# TUE-JJ-9-1.net
KiCad netlist of a schematic drawn in EAGLE
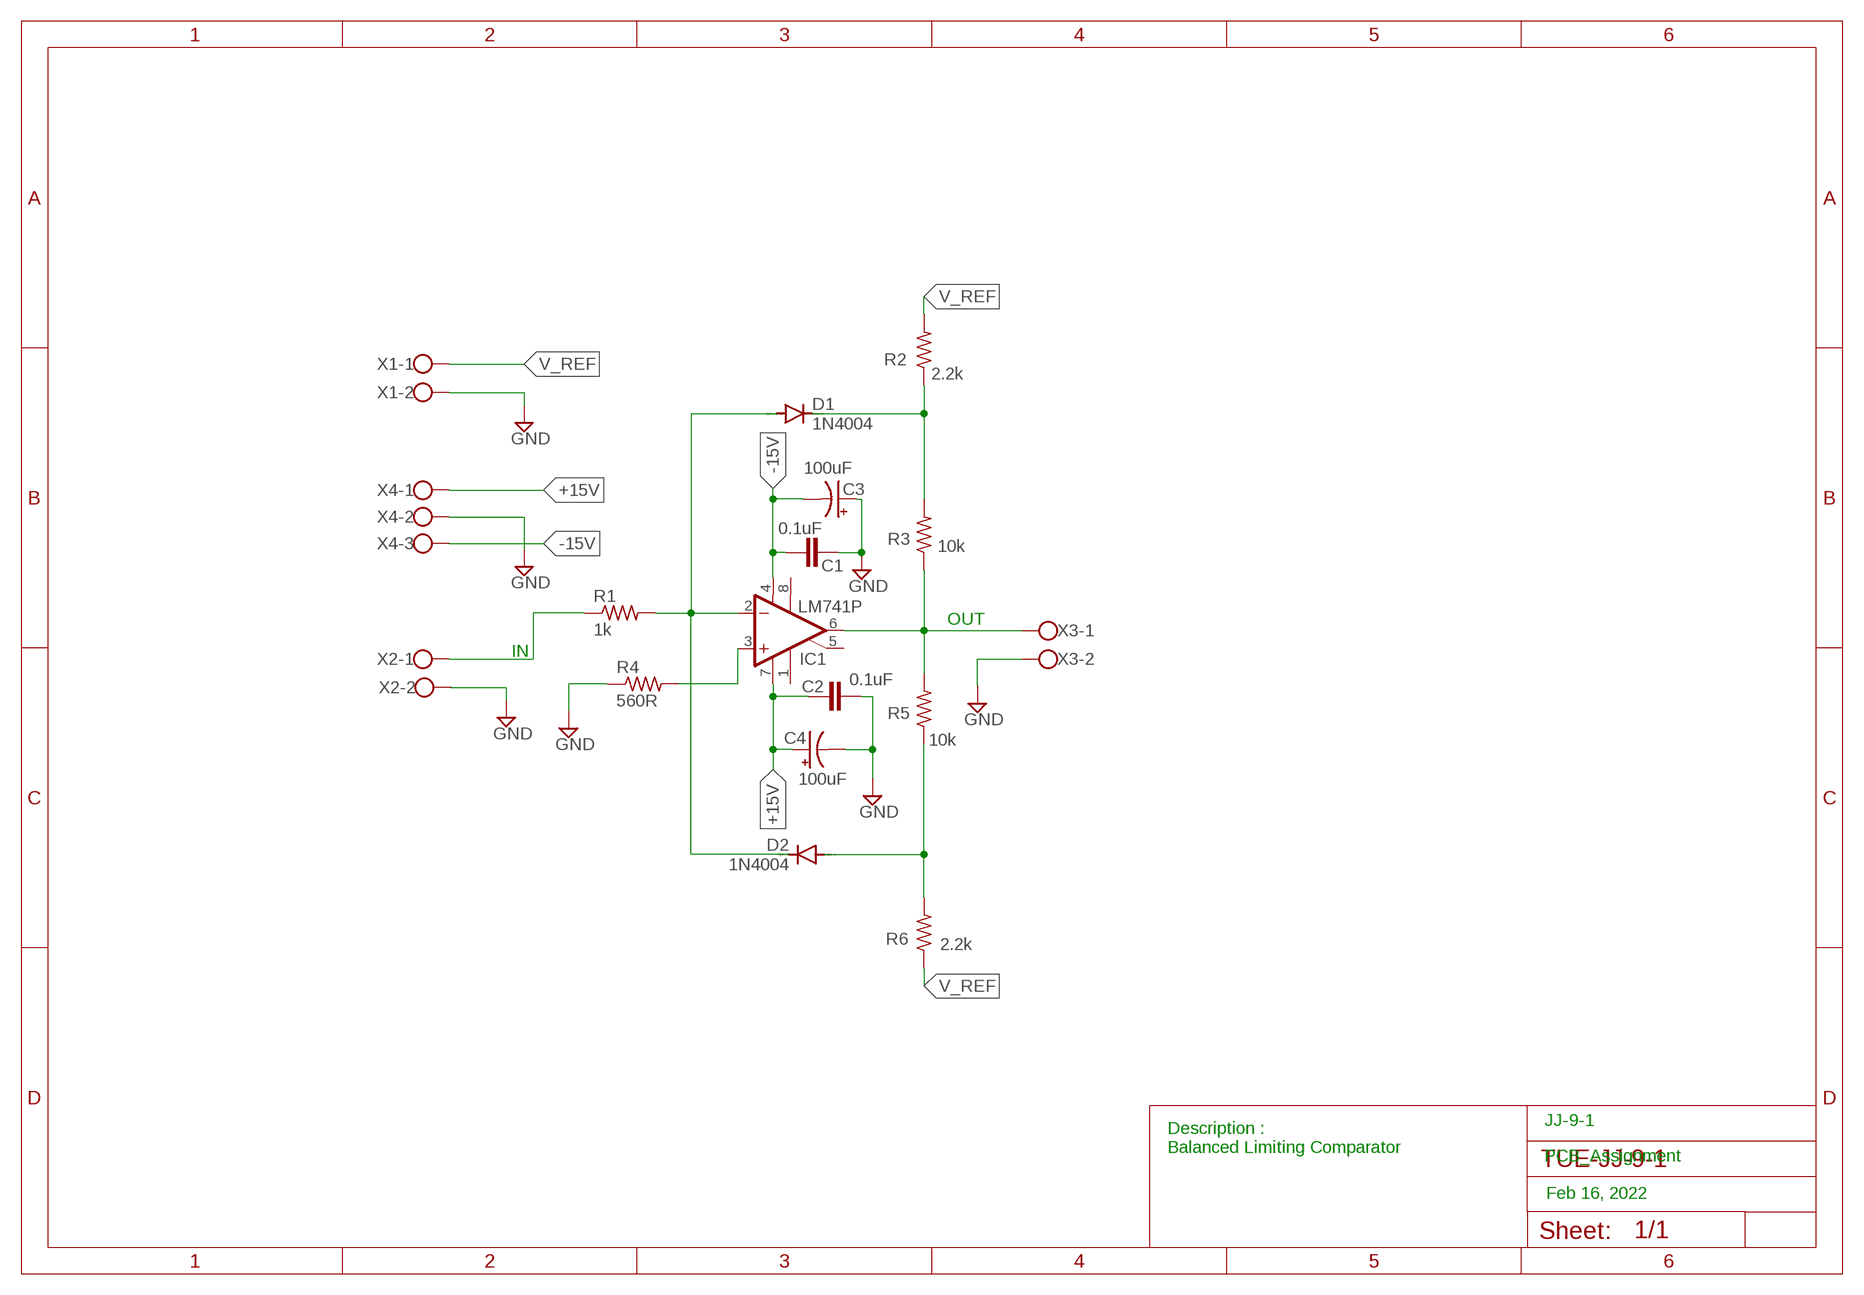
[diagram p0: schematic, sheet 1]

(export (version "E")
  (design (tool "Eeschema 10.0.6"))
  (components
    (comp (ref "C1")
      (value "0.1uF")
      (footprint "eagle-import:C050-025X075")
      (libsource (lib "eagle-import") (part "C-EU050-025X075"))
    )
    (comp (ref "C2")
      (value "0.1uF")
      (footprint "eagle-import:C050-025X075")
      (libsource (lib "eagle-import") (part "C-EU050-025X075"))
    )
    (comp (ref "C3")
      (value "100uF")
      (footprint "eagle-import:E2,5-7")
      (libsource (lib "eagle-import") (part "CPOL-USE2.5-7"))
    )
    (comp (ref "C4")
      (value "100uF")
      (footprint "eagle-import:E2,5-7")
      (libsource (lib "eagle-import") (part "CPOL-USE2.5-7"))
    )
    (comp (ref "D1")
      (value "1N4004")
      (footprint "eagle-import:DO41-10")
      (libsource (lib "eagle-import") (part "1N4004"))
    )
    (comp (ref "D2")
      (value "1N4004")
      (footprint "eagle-import:DO41-10")
      (libsource (lib "eagle-import") (part "1N4004"))
    )
    (comp (ref "IC1")
      (value "LM741P")
      (footprint "eagle-import:DIL08")
      (libsource (lib "eagle-import") (part "741PLM"))
    )
    (comp (ref "R1")
      (value "1k")
      (footprint "eagle-import:0207_10")
      (libsource (lib "eagle-import") (part "R-US_0207/10"))
    )
    (comp (ref "R2")
      (value "2.2k")
      (footprint "eagle-import:0207_10")
      (libsource (lib "eagle-import") (part "R-US_0207/10"))
    )
    (comp (ref "R3")
      (value "10k")
      (footprint "eagle-import:0207_10")
      (libsource (lib "eagle-import") (part "R-US_0207/10"))
    )
    (comp (ref "R4")
      (value "560R")
      (footprint "eagle-import:0207_10")
      (libsource (lib "eagle-import") (part "R-US_0207/10"))
    )
    (comp (ref "R5")
      (value "10k")
      (footprint "eagle-import:0207_10")
      (libsource (lib "eagle-import") (part "R-US_0207/10"))
    )
    (comp (ref "R6")
      (value "2.2k")
      (footprint "eagle-import:0207_10")
      (libsource (lib "eagle-import") (part "R-US_0207/10"))
    )
    (comp (ref "X1")
      (value "W237-102")
      (footprint "eagle-import:W237-102")
      (fields (field (name "MPN") "237-102"))
      (libsource (lib "eagle-import") (part "W237-102"))
    )
    (comp (ref "X2")
      (value "W237-102")
      (footprint "eagle-import:W237-102")
      (fields (field (name "MPN") "237-102"))
      (libsource (lib "eagle-import") (part "W237-102"))
    )
    (comp (ref "X3")
      (value "W237-102")
      (footprint "eagle-import:W237-102")
      (fields (field (name "MPN") "237-102"))
      (libsource (lib "eagle-import") (part "W237-102"))
    )
    (comp (ref "X4")
      (value "W237-103")
      (footprint "eagle-import:W237-103")
      (fields (field (name "MPN") "237-103"))
      (libsource (lib "eagle-import") (part "W237-103"))
    )
  )
  (nets
    (net (code "1") (name "+15V") (class "Default")
      (node (ref "C2") (pin "1") (pinfunction "1_1") (pintype "passive"))
      (node (ref "C4") (pin "+") (pinfunction "+_+") (pintype "passive"))
      (node (ref "IC1") (pin "7") (pinfunction "V+_7") (pintype "power_in"))
      (node (ref "X4") (pin "1") (pinfunction "KL_1") (pintype "passive"))
    )
    (net (code "2") (name "-15V") (class "Default")
      (node (ref "C1") (pin "1") (pinfunction "1_1") (pintype "passive"))
      (node (ref "C3") (pin "-") (pinfunction "-_-") (pintype "passive"))
      (node (ref "IC1") (pin "4") (pinfunction "V-_4") (pintype "power_in"))
      (node (ref "X4") (pin "3") (pinfunction "KL_3") (pintype "passive"))
    )
    (net (code "3") (name "GND") (class "Default")
      (node (ref "C1") (pin "2") (pinfunction "2_2") (pintype "passive"))
      (node (ref "C2") (pin "2") (pinfunction "2_2") (pintype "passive"))
      (node (ref "C3") (pin "+") (pinfunction "+_+") (pintype "passive"))
      (node (ref "C4") (pin "-") (pinfunction "-_-") (pintype "passive"))
      (node (ref "R4") (pin "1") (pinfunction "1_1") (pintype "passive"))
      (node (ref "X1") (pin "2") (pinfunction "KL_2") (pintype "passive"))
      (node (ref "X2") (pin "2") (pinfunction "KL_2") (pintype "passive"))
      (node (ref "X3") (pin "2") (pinfunction "KL_2") (pintype "passive"))
      (node (ref "X4") (pin "2") (pinfunction "KL_2") (pintype "passive"))
    )
    (net (code "4") (name "Net-(D1-PadC)") (class "Default")
      (node (ref "D1") (pin "C") (pinfunction "C_C") (pintype "passive"))
      (node (ref "R2") (pin "1") (pinfunction "1_1") (pintype "passive"))
      (node (ref "R3") (pin "2") (pinfunction "2_2") (pintype "passive"))
    )
    (net (code "5") (name "Net-(D2-PadA)") (class "Default")
      (node (ref "D2") (pin "A") (pinfunction "A_A") (pintype "passive"))
      (node (ref "R5") (pin "1") (pinfunction "1_1") (pintype "passive"))
      (node (ref "R6") (pin "2") (pinfunction "2_2") (pintype "passive"))
    )
    (net (code "6") (name "Net-(IC1-+IN)") (class "Default")
      (node (ref "IC1") (pin "3") (pinfunction "+IN_3") (pintype "input"))
      (node (ref "R4") (pin "2") (pinfunction "2_2") (pintype "passive"))
    )
    (net (code "7") (name "Net-(IC1--IN)") (class "Default")
      (node (ref "D1") (pin "A") (pinfunction "A_A") (pintype "passive"))
      (node (ref "D2") (pin "C") (pinfunction "C_C") (pintype "passive"))
      (node (ref "IC1") (pin "2") (pinfunction "-IN_2") (pintype "input"))
      (node (ref "R1") (pin "2") (pinfunction "2_2") (pintype "passive"))
    )
    (net (code "8") (name "Net-(IC1-OUT)") (class "Default")
      (node (ref "IC1") (pin "6") (pinfunction "OUT_6") (pintype "output"))
      (node (ref "R3") (pin "1") (pinfunction "1_1") (pintype "passive"))
      (node (ref "R5") (pin "2") (pinfunction "2_2") (pintype "passive"))
      (node (ref "X3") (pin "1") (pinfunction "KL_1") (pintype "passive"))
    )
    (net (code "9") (name "Net-(X2A-KL)") (class "Default")
      (node (ref "R1") (pin "1") (pinfunction "1_1") (pintype "passive"))
      (node (ref "X2") (pin "1") (pinfunction "KL_1") (pintype "passive"))
    )
    (net (code "10") (name "V_REF") (class "Default")
      (node (ref "R2") (pin "2") (pinfunction "2_2") (pintype "passive"))
      (node (ref "R6") (pin "1") (pinfunction "1_1") (pintype "passive"))
      (node (ref "X1") (pin "1") (pinfunction "KL_1") (pintype "passive"))
    )
    (net (code "11") (name "unconnected-(IC1-ON1-Pad1)") (class "Default")
      (node (ref "IC1") (pin "1") (pinfunction "ON1_1") (pintype "passive"))
    )
    (net (code "12") (name "unconnected-(IC1-ON2-Pad5)") (class "Default")
      (node (ref "IC1") (pin "5") (pinfunction "ON2_5") (pintype "passive"))
    )
    (net (code "13") (name "unconnected-(IC1-OPT-Pad8)") (class "Default")
      (node (ref "IC1") (pin "8") (pinfunction "OPT_8") (pintype "passive"))
    )
  )
)
